# main.net
KiCad netlist of a schematic drawn in Altium Designer
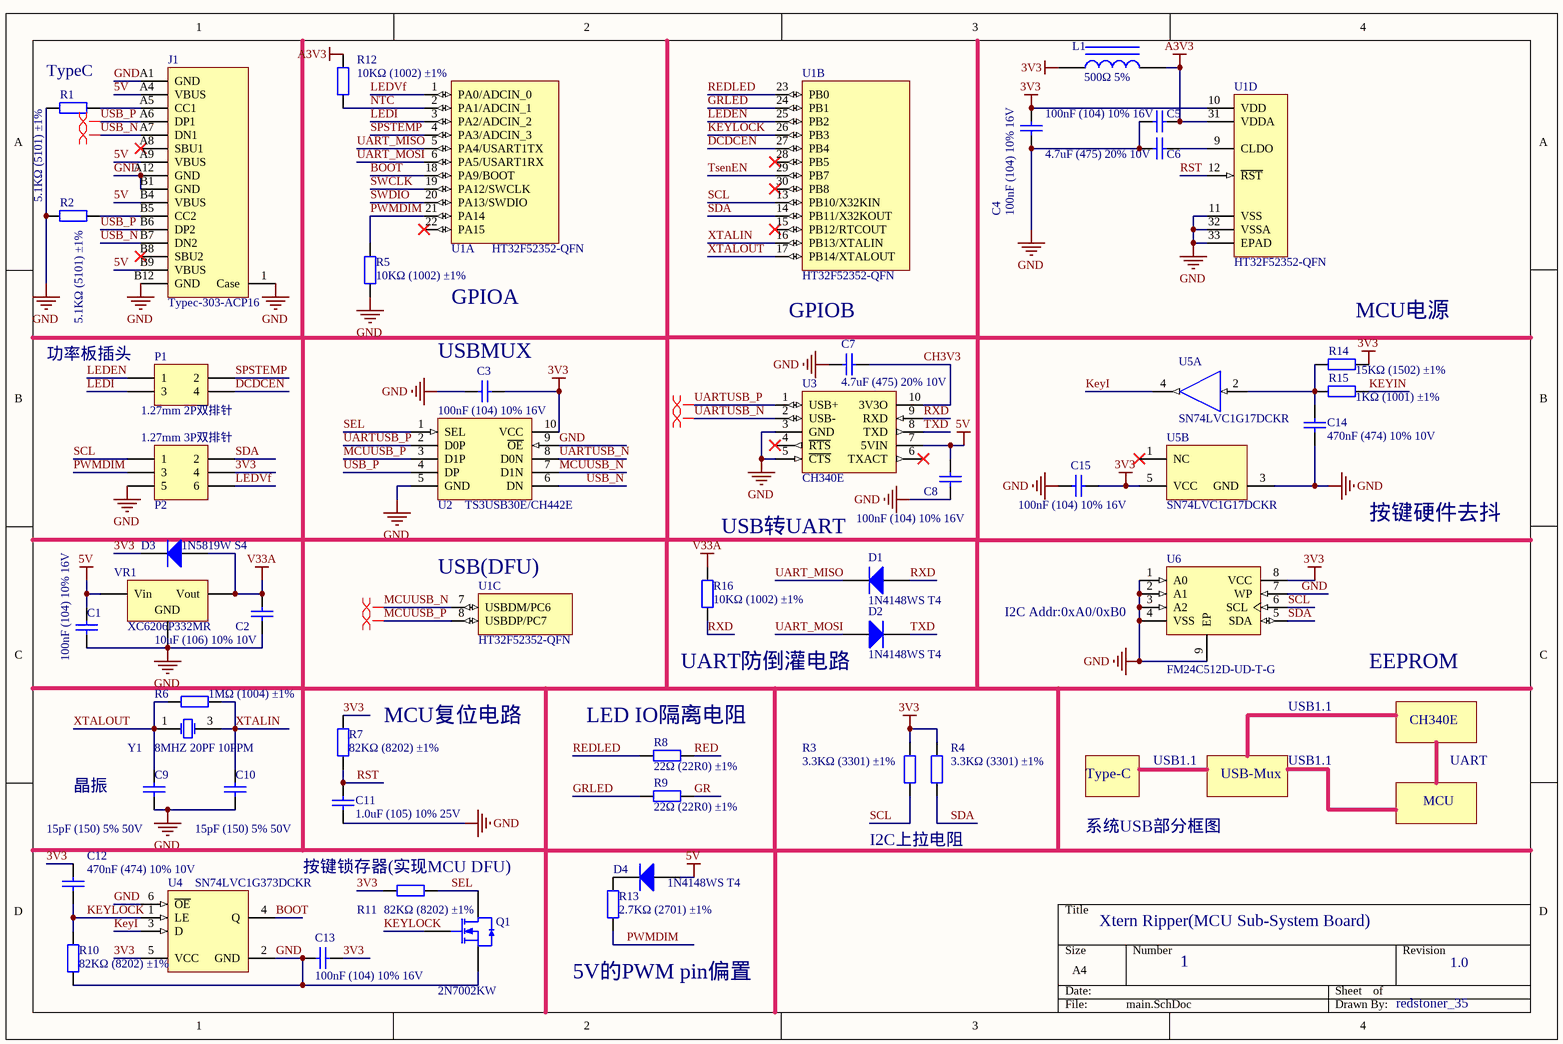
[diagram p0: main.SchDoc]

(export (version "E")
  (design (tool "Eeschema 10.0.6"))
  (components
    (comp (ref "C1")
      (value "100nF (104) 10% 16V")
      (footprint "0402_C")
      (description "贴片电容")
      (libsource (lib "Miscellaneous Devices LC") (part "0402 100nF (104) 10% 16V"))
    )
    (comp (ref "C2")
      (value "10uF (106) 10% 10V")
      (footprint "0603_C")
      (description "贴片电容")
      (libsource (lib "Miscellaneous Devices LC") (part "0603 10uF (106) 10% 10V"))
    )
    (comp (ref "C3")
      (value "100nF (104) 10% 16V")
      (footprint "0402_C")
      (description "贴片电容")
      (libsource (lib "Miscellaneous Devices LC") (part "0402 100nF (104) 10% 16V"))
    )
    (comp (ref "C4")
      (value "100nF (104) 10% 16V")
      (footprint "0402_C")
      (description "贴片电容")
      (libsource (lib "Miscellaneous Devices LC") (part "0402 100nF (104) 10% 16V"))
    )
    (comp (ref "C5")
      (value "100nF (104) 10% 16V")
      (footprint "0402_C")
      (description "贴片电容")
      (libsource (lib "Miscellaneous Devices LC") (part "0402 100nF (104) 10% 16V"))
    )
    (comp (ref "C6")
      (value "4.7uF (475) 20% 10V")
      (footprint "0402_C")
      (description "贴片电容")
      (libsource (lib "Miscellaneous Devices LC") (part "0402 4.7uF (475) 20% 10V"))
    )
    (comp (ref "C7")
      (value "4.7uF (475) 20% 10V")
      (footprint "0402_C")
      (description "贴片电容")
      (libsource (lib "Miscellaneous Devices LC") (part "0402 4.7uF (475) 20% 10V"))
    )
    (comp (ref "C8")
      (value "100nF (104) 10% 16V")
      (footprint "0402_C")
      (description "贴片电容")
      (libsource (lib "Miscellaneous Devices LC") (part "0402 100nF (104) 10% 16V"))
    )
    (comp (ref "C9")
      (value "15pF (150) 5% 50V")
      (footprint "0402_C")
      (description "贴片电容")
      (libsource (lib "Miscellaneous Devices LC") (part "0402 15pF (150) 5% 50V"))
    )
    (comp (ref "C10")
      (value "15pF (150) 5% 50V")
      (footprint "0402_C")
      (description "贴片电容")
      (libsource (lib "Miscellaneous Devices LC") (part "0402 15pF (150) 5% 50V"))
    )
    (comp (ref "C11")
      (value "1.0uF (105) 10% 25V")
      (footprint "0402_C")
      (description "贴片电容")
      (libsource (lib "Miscellaneous Devices LC") (part "0402 1.0uF (105) 10% 25V"))
    )
    (comp (ref "C12")
      (value "470nF (474) 10% 10V")
      (footprint "0402_C")
      (description "贴片电容")
      (libsource (lib "Miscellaneous Devices LC") (part "0402 470nF (474) 10% 10V"))
    )
    (comp (ref "C13")
      (value "100nF (104) 10% 16V")
      (footprint "0402_C")
      (description "贴片电容")
      (libsource (lib "Miscellaneous Devices LC") (part "0402 100nF (104) 10% 16V"))
    )
    (comp (ref "C14")
      (value "470nF (474) 10% 10V")
      (footprint "0402_C")
      (description "贴片电容")
      (libsource (lib "Miscellaneous Devices LC") (part "0402 470nF (474) 10% 10V"))
    )
    (comp (ref "C15")
      (value "100nF (104) 10% 16V")
      (footprint "0402_C")
      (description "贴片电容")
      (libsource (lib "Miscellaneous Devices LC") (part "0402 100nF (104) 10% 16V"))
    )
    (comp (ref "D1")
      (value "1N4148WS T4")
      (footprint "SOD-323")
      (description "二极管")
      (libsource (lib "Miscellaneous Devices LC") (part "SOD-323 1N4148WS T4"))
    )
    (comp (ref "D2")
      (value "1N4148WS T4")
      (footprint "SOD-323")
      (description "二极管")
      (libsource (lib "Miscellaneous Devices LC") (part "SOD-323 1N4148WS T4"))
    )
    (comp (ref "D3")
      (value "1N5819W S4")
      (footprint "SOD-323")
      (description "二极管")
      (libsource (lib "Miscellaneous Devices LC") (part "SOD-323 1N4148WS T4"))
    )
    (comp (ref "D4")
      (value "1N4148WS T4")
      (footprint "SOD-323")
      (description "二极管")
      (libsource (lib "Miscellaneous Devices LC") (part "SOD-323 1N4148WS T4"))
    )
    (comp (ref "J1")
      (value "Typec-303-ACP16")
      (footprint "USB-C-SMD_TYPEC-303-ACP16")
      (description "16Pin TypeC 立贴母座")
      (libsource (lib "custom") (part "Type-303-ACP16"))
    )
    (comp (ref "L1")
      (value "500Ω 5%")
      (footprint "0402_L")
      (description "贴片磁珠")
      (libsource (lib "Miscellaneous Devices LC") (part "0402 10nH 5%"))
    )
    (comp (ref "P1")
      (value "1.27mm 2P双排针")
      (footprint "MHDR2X2")
      (description "Header, 2-Pin, Dual row")
      (fields (field (name "PUBLISHER") "Altium Limited"))
      (libsource (lib "Miscellaneous Connectors") (part "MHDR2X2"))
    )
    (comp (ref "P2")
      (value "1.27mm 3P双排针")
      (footprint "MHDR2X3")
      (description "Header, 3-Pin, Dual row")
      (fields (field (name "PUBLISHER") "Altium Limited"))
      (libsource (lib "Miscellaneous Connectors") (part "MHDR2X3"))
    )
    (comp (ref "Q1")
      (value "2N7002KW")
      (footprint "SC70-3")
      (description "MOS(场效应管)")
      (libsource (lib "Miscellaneous Devices LC") (part "2N7002 7002"))
    )
    (comp (ref "R1")
      (value "5.1KΩ (5101) ±1%")
      (footprint "0402_R")
      (description "贴片电阻")
      (libsource (lib "Miscellaneous Devices LC") (part "0402 5.1KΩ (5101) 1%"))
    )
    (comp (ref "R2")
      (value "5.1KΩ (5101) ±1%")
      (footprint "0402_R")
      (description "贴片电阻")
      (libsource (lib "Miscellaneous Devices LC") (part "0402 5.1KΩ (5101) 1%"))
    )
    (comp (ref "R3")
      (value "3.3KΩ (3301) ±1%")
      (footprint "0402_R")
      (description "贴片电阻")
      (libsource (lib "Miscellaneous Devices LC") (part "0402 3.3KΩ (3301) 1%"))
    )
    (comp (ref "R4")
      (value "3.3KΩ (3301) ±1%")
      (footprint "0402_R")
      (description "贴片电阻")
      (libsource (lib "Miscellaneous Devices LC") (part "0402 3.3KΩ (3301) 1%"))
    )
    (comp (ref "R5")
      (value "10KΩ (1002) ±1%")
      (footprint "0402_R")
      (description "贴片电阻")
      (libsource (lib "Miscellaneous Devices LC") (part "0402 10KΩ (1002) 1%"))
    )
    (comp (ref "R6")
      (value "1MΩ (1004) ±1%")
      (footprint "0402_R")
      (description "贴片电阻")
      (libsource (lib "Miscellaneous Devices LC") (part "0402 1MΩ (1004) 1%"))
    )
    (comp (ref "R7")
      (value "82KΩ (8202) ±1%")
      (footprint "0402_R")
      (description "贴片电阻")
      (libsource (lib "Miscellaneous Devices LC") (part "0402 68KΩ (6802) 1%"))
    )
    (comp (ref "R8")
      (value "22Ω (22R0) ±1%")
      (footprint "0402_R")
      (description "贴片电阻")
      (libsource (lib "Miscellaneous Devices LC") (part "0402 22Ω (22R0) 1%"))
    )
    (comp (ref "R9")
      (value "22Ω (22R0) ±1%")
      (footprint "0402_R")
      (description "贴片电阻")
      (libsource (lib "Miscellaneous Devices LC") (part "0402 22Ω (22R0) 1%"))
    )
    (comp (ref "R10")
      (value "82KΩ (8202) ±1%")
      (footprint "0402_R")
      (description "贴片电阻")
      (libsource (lib "Miscellaneous Devices LC") (part "0402 68KΩ (6802) 1%"))
    )
    (comp (ref "R11")
      (value "82KΩ (8202) ±1%")
      (footprint "0402_R")
      (description "贴片电阻")
      (libsource (lib "Miscellaneous Devices LC") (part "0402 100KΩ (1003) 1%"))
    )
    (comp (ref "R12")
      (value "10KΩ (1002) ±1%")
      (footprint "0402_R")
      (description "贴片电阻")
      (libsource (lib "Miscellaneous Devices LC") (part "0402 10KΩ (1002) 1%"))
    )
    (comp (ref "R13")
      (value "2.7KΩ (2701) ±1%")
      (footprint "0402_R")
      (description "贴片电阻")
      (libsource (lib "Miscellaneous Devices LC") (part "0402 3.3KΩ (3301) 1%"))
    )
    (comp (ref "R14")
      (value "15KΩ (1502) ±1%")
      (footprint "0402_R")
      (description "贴片电阻")
      (libsource (lib "Miscellaneous Devices LC") (part "0402 15KΩ (1502) 1%"))
    )
    (comp (ref "R15")
      (value "1KΩ (1001) ±1%")
      (footprint "0402_R")
      (description "贴片电阻")
      (libsource (lib "Miscellaneous Devices LC") (part "0402 1KΩ (1001) 1%"))
    )
    (comp (ref "R16")
      (value "10KΩ (1002) ±1%")
      (footprint "0402_R")
      (description "贴片电阻")
      (libsource (lib "Miscellaneous Devices LC") (part "0402 10KΩ (1002) 1%"))
    )
    (comp (ref "U1")
      (value "HT32F52352-QFN")
      (footprint "QFN32-HT32")
      (description "Holtek MCU Cortex M0+ 48MHz 128K ROM 16K RAM")
      (libsource (lib "custom") (part "HT32F52352-QFN"))
    )
    (comp (ref "U2")
      (value "TS3USB30E/CH442E")
      (footprint "MSOP-10")
      (description "Passive SPDT USB2.0 Highspeed switch")
      (libsource (lib "custom") (part "TS3USB30E"))
    )
    (comp (ref "U3")
      (value "CH340E")
      (footprint "MSOP-10")
      (description "USB-TTL UART converter MSOP-10")
      (libsource (lib "custom") (part "CH340E"))
    )
    (comp (ref "U4")
      (value "SN74LVC1G373DCKR")
      (footprint "DCK0006A_N")
      (description "Single D-Type Latch with 3S Output, DCK0006A, LARGE T&R")
      (fields
        (field (name "GENERIC PART NUMBER") "SN74LVC1G373")
        (field (name "MANUFACTURER") "Texas Instruments")
      )
      (libsource (lib "TI_Logic_Little_Logic") (part "SN74LVC1G373DCKR"))
    )
    (comp (ref "U5")
      (value "SN74LVC1G17DCKR")
      (footprint "DCK0005A_N")
      (description "Single Schmitt-Trigger Buffer, DCK0005A, LARGE T&R")
      (fields
        (field (name "GENERIC PART NUMBER") "SN74LVC1G17")
        (field (name "MANUFACTURER") "Texas Instruments")
      )
      (libsource (lib "") (part "SN74LVC1G17DCKR_1"))
    )
    (comp (ref "U6")
      (value "FM24C512D-UD-T-G")
      (footprint "UDFN-8")
      (description "512Kbit 24Serires I2C EEPROM UDFN-8 with UID and OTP Sector")
      (libsource (lib "custom") (part "CAT24C512HU5"))
    )
    (comp (ref "VR1")
      (value "XC6206P332MR")
      (footprint "SOT-23-3L")
      (description "低压差线性稳压(LDO)")
      (libsource (lib "Miscellaneous Devices LC") (part "SOT-23 XC6206P332MR"))
    )
    (comp (ref "Y1")
      (value "8MHZ 20PF 10PPM")
      (footprint "SMD-3225_4P")
      (description "贴片晶振")
      (libsource (lib "Miscellaneous Devices LC") (part "SMD-3225_4P  12MHZ 20PF 10PPM"))
    )
  )
  (nets
    (net (code "1") (name "/BOOT") (class "Default")
      (node (ref "U1") (pin "18") (pinfunction "PA9/BOOT_18") (pintype "bidirectional"))
      (node (ref "U4") (pin "4") (pinfunction "Q_4") (pintype "tri_state"))
    )
    (net (code "2") (name "/CH3V3") (class "Default")
      (node (ref "C7") (pin "1") (pinfunction "1_1") (pintype "passive"))
      (node (ref "U3") (pin "10") (pinfunction "3V3O_10") (pintype "power_in"))
    )
    (net (code "3") (name "/DCDCEN") (class "Default")
      (node (ref "P1") (pin "4") (pinfunction "4_4") (pintype "passive"))
      (node (ref "U1") (pin "27") (pinfunction "PB4_27") (pintype "bidirectional"))
    )
    (net (code "4") (name "/GR") (class "Default")
      (node (ref "R9") (pin "2") (pinfunction "2_2") (pintype "passive"))
    )
    (net (code "5") (name "/GRLED") (class "Default")
      (node (ref "R9") (pin "1") (pinfunction "1_1") (pintype "passive"))
      (node (ref "U1") (pin "24") (pinfunction "PB1_24") (pintype "bidirectional"))
    )
    (net (code "6") (name "/KEYIN") (class "Default")
      (node (ref "R15") (pin "2") (pinfunction "2_2") (pintype "passive"))
    )
    (net (code "7") (name "/KEYLOCK") (class "Default")
      (node (ref "C12") (pin "1") (pinfunction "1_1") (pintype "passive"))
      (node (ref "Q1") (pin "1") (pinfunction "G_1") (pintype "passive"))
      (node (ref "R10") (pin "2") (pinfunction "2_2") (pintype "passive"))
      (node (ref "U1") (pin "26") (pinfunction "PB3_26") (pintype "bidirectional"))
      (node (ref "U4") (pin "1") (pinfunction "LE_1") (pintype "input"))
    )
    (net (code "8") (name "/KeyI") (class "Default")
      (node (ref "U4") (pin "3") (pinfunction "D_3") (pintype "input"))
      (node (ref "U5") (pin "4") (pinfunction "Y_4") (pintype "output"))
    )
    (net (code "9") (name "/LEDEN") (class "Default")
      (node (ref "P1") (pin "1") (pinfunction "1_1") (pintype "passive"))
      (node (ref "U1") (pin "25") (pinfunction "PB2_25") (pintype "bidirectional"))
    )
    (net (code "10") (name "/LEDI") (class "Default")
      (node (ref "P1") (pin "3") (pinfunction "3_3") (pintype "passive"))
      (node (ref "U1") (pin "3") (pinfunction "PA2/ADCIN_2_3") (pintype "bidirectional"))
    )
    (net (code "11") (name "/LEDVf") (class "Default")
      (node (ref "P2") (pin "6") (pinfunction "6_6") (pintype "passive"))
      (node (ref "U1") (pin "1") (pinfunction "PA0/ADCIN_0_1") (pintype "bidirectional"))
    )
    (net (code "12") (name "/MCUUSB_N") (class "Default")
      (node (ref "U1") (pin "7") (pinfunction "USBDM/PC6_7") (pintype "bidirectional"))
      (node (ref "U2") (pin "7") (pinfunction "D1N_7") (pintype "passive"))
    )
    (net (code "13") (name "/MCUUSB_P") (class "Default")
      (node (ref "U1") (pin "8") (pinfunction "USBDP/PC7_8") (pintype "bidirectional"))
      (node (ref "U2") (pin "3") (pinfunction "D1P_3") (pintype "passive"))
    )
    (net (code "14") (name "/NTC") (class "Default")
      (node (ref "R12") (pin "1") (pinfunction "1_1") (pintype "passive"))
      (node (ref "U1") (pin "2") (pinfunction "PA1/ADCIN_1_2") (pintype "bidirectional"))
    )
    (net (code "15") (name "/PWMDIM") (class "Default")
      (node (ref "P2") (pin "3") (pinfunction "3_3") (pintype "passive"))
      (node (ref "R13") (pin "1") (pinfunction "1_1") (pintype "passive"))
      (node (ref "R5") (pin "2") (pinfunction "2_2") (pintype "passive"))
      (node (ref "U1") (pin "21") (pinfunction "PA14_21") (pintype "bidirectional"))
    )
    (net (code "16") (name "/RED") (class "Default")
      (node (ref "R8") (pin "2") (pinfunction "2_2") (pintype "passive"))
    )
    (net (code "17") (name "/REDLED") (class "Default")
      (node (ref "R8") (pin "1") (pinfunction "1_1") (pintype "passive"))
      (node (ref "U1") (pin "23") (pinfunction "PB0_23") (pintype "bidirectional"))
    )
    (net (code "18") (name "/RST") (class "Default")
      (node (ref "C11") (pin "2") (pinfunction "2_2") (pintype "passive"))
      (node (ref "R7") (pin "1") (pinfunction "1_1") (pintype "passive"))
      (node (ref "U1") (pin "12") (pinfunction "~{RST}_12") (pintype "input"))
    )
    (net (code "19") (name "/RXD") (class "Default")
      (node (ref "D1") (pin "1") (pinfunction "A_1") (pintype "passive"))
      (node (ref "R16") (pin "1") (pinfunction "1_1") (pintype "passive"))
      (node (ref "U3") (pin "9") (pinfunction "RXD_9") (pintype "input"))
    )
    (net (code "20") (name "/SCL") (class "Default")
      (node (ref "P2") (pin "1") (pinfunction "1_1") (pintype "passive"))
      (node (ref "R3") (pin "1") (pinfunction "1_1") (pintype "passive"))
      (node (ref "U1") (pin "13") (pinfunction "PB10/X32KIN_13") (pintype "bidirectional"))
      (node (ref "U6") (pin "6") (pinfunction "SCL_6") (pintype "input"))
    )
    (net (code "21") (name "/SDA") (class "Default")
      (node (ref "P2") (pin "2") (pinfunction "2_2") (pintype "passive"))
      (node (ref "R4") (pin "1") (pinfunction "1_1") (pintype "passive"))
      (node (ref "U1") (pin "14") (pinfunction "PB11/X32KOUT_14") (pintype "bidirectional"))
      (node (ref "U6") (pin "5") (pinfunction "SDA_5") (pintype "bidirectional"))
    )
    (net (code "22") (name "/SEL") (class "Default")
      (node (ref "Q1") (pin "3") (pinfunction "D_3") (pintype "passive"))
      (node (ref "R11") (pin "2") (pinfunction "2_2") (pintype "passive"))
      (node (ref "U2") (pin "1") (pinfunction "SEL_1") (pintype "input"))
    )
    (net (code "23") (name "/SPSTEMP") (class "Default")
      (node (ref "P1") (pin "2") (pinfunction "2_2") (pintype "passive"))
      (node (ref "U1") (pin "4") (pinfunction "PA3/ADCIN_3_4") (pintype "bidirectional"))
    )
    (net (code "24") (name "/SWCLK") (class "Default")
      (node (ref "U1") (pin "19") (pinfunction "PA12/SWCLK_19") (pintype "bidirectional"))
    )
    (net (code "25") (name "/SWDIO") (class "Default")
      (node (ref "U1") (pin "20") (pinfunction "PA13/SWDIO_20") (pintype "bidirectional"))
    )
    (net (code "26") (name "/TXD") (class "Default")
      (node (ref "D2") (pin "2") (pinfunction "K_2") (pintype "passive"))
      (node (ref "U3") (pin "8") (pinfunction "TXD_8") (pintype "output"))
    )
    (net (code "27") (name "/TsenEN") (class "Default")
      (node (ref "U1") (pin "29") (pinfunction "PB7_29") (pintype "bidirectional"))
    )
    (net (code "28") (name "/UARTUSB_N") (class "Default")
      (node (ref "U2") (pin "8") (pinfunction "D0N_8") (pintype "passive"))
      (node (ref "U3") (pin "2") (pinfunction "USB-_2") (pintype "bidirectional"))
    )
    (net (code "29") (name "/UARTUSB_P") (class "Default")
      (node (ref "U2") (pin "2") (pinfunction "D0P_2") (pintype "passive"))
      (node (ref "U3") (pin "1") (pinfunction "USB+_1") (pintype "bidirectional"))
    )
    (net (code "30") (name "/UART_MISO") (class "Default")
      (node (ref "D1") (pin "2") (pinfunction "K_2") (pintype "passive"))
      (node (ref "U1") (pin "5") (pinfunction "PA4/USART1TX_5") (pintype "bidirectional"))
    )
    (net (code "31") (name "/UART_MOSI") (class "Default")
      (node (ref "D2") (pin "1") (pinfunction "A_1") (pintype "passive"))
      (node (ref "U1") (pin "6") (pinfunction "PA5/USART1RX_6") (pintype "bidirectional"))
    )
    (net (code "32") (name "/USB_N") (class "Default")
      (node (ref "J1") (pin "A7") (pinfunction "DN1_A7") (pintype "passive"))
      (node (ref "J1") (pin "B7") (pinfunction "DN2_B7") (pintype "passive"))
      (node (ref "U2") (pin "6") (pinfunction "DN_6") (pintype "power_in"))
    )
    (net (code "33") (name "/USB_P") (class "Default")
      (node (ref "J1") (pin "A6") (pinfunction "DP1_A6") (pintype "passive"))
      (node (ref "J1") (pin "B6") (pinfunction "DP2_B6") (pintype "passive"))
      (node (ref "U2") (pin "4") (pinfunction "DP_4") (pintype "passive"))
    )
    (net (code "34") (name "/XTALIN") (class "Default")
      (node (ref "C10") (pin "2") (pinfunction "2_2") (pintype "passive"))
      (node (ref "R6") (pin "2") (pinfunction "2_2") (pintype "passive"))
      (node (ref "U1") (pin "16") (pinfunction "PB13/XTALIN_16") (pintype "bidirectional"))
      (node (ref "Y1") (pin "3") (pinfunction "OSC2_3") (pintype "passive"))
    )
    (net (code "35") (name "/XTALOUT") (class "Default")
      (node (ref "C9") (pin "2") (pinfunction "2_2") (pintype "passive"))
      (node (ref "R6") (pin "1") (pinfunction "1_1") (pintype "passive"))
      (node (ref "U1") (pin "17") (pinfunction "PB14/XTALOUT_17") (pintype "bidirectional"))
      (node (ref "Y1") (pin "1") (pinfunction "OSC1_1") (pintype "passive"))
    )
    (net (code "36") (name "3V3") (class "Default")
      (node (ref "C12") (pin "2") (pinfunction "2_2") (pintype "passive"))
      (node (ref "C13") (pin "1") (pinfunction "1_1") (pintype "passive"))
      (node (ref "C15") (pin "2") (pinfunction "2_2") (pintype "passive"))
      (node (ref "C3") (pin "2") (pinfunction "2_2") (pintype "passive"))
      (node (ref "C4") (pin "2") (pinfunction "2_2") (pintype "passive"))
      (node (ref "D3") (pin "2") (pinfunction "K_2") (pintype "passive"))
      (node (ref "L1") (pin "1") (pinfunction "1_1") (pintype "passive"))
      (node (ref "P2") (pin "4") (pinfunction "4_4") (pintype "passive"))
      (node (ref "R11") (pin "1") (pinfunction "1_1") (pintype "passive"))
      (node (ref "R14") (pin "1") (pinfunction "1_1") (pintype "passive"))
      (node (ref "R3") (pin "2") (pinfunction "2_2") (pintype "passive"))
      (node (ref "R4") (pin "2") (pinfunction "2_2") (pintype "passive"))
      (node (ref "R7") (pin "2") (pinfunction "2_2") (pintype "passive"))
      (node (ref "U1") (pin "10") (pinfunction "VDD_10") (pintype "power_in"))
      (node (ref "U2") (pin "10") (pinfunction "VCC_10") (pintype "power_in"))
      (node (ref "U4") (pin "5") (pinfunction "VCC_5") (pintype "power_in"))
      (node (ref "U5") (pin "5") (pinfunction "VCC_5") (pintype "power_in"))
      (node (ref "U6") (pin "8") (pinfunction "VCC_8") (pintype "power_in"))
    )
    (net (code "37") (name "5V") (class "Default")
      (node (ref "C1") (pin "2") (pinfunction "2_2") (pintype "passive"))
      (node (ref "C8") (pin "2") (pinfunction "2_2") (pintype "passive"))
      (node (ref "D4") (pin "1") (pinfunction "A_1") (pintype "passive"))
      (node (ref "J1") (pin "A4") (pinfunction "VBUS_A4") (pintype "passive"))
      (node (ref "J1") (pin "A9") (pinfunction "VBUS_A9") (pintype "passive"))
      (node (ref "J1") (pin "B4") (pinfunction "VBUS_B4") (pintype "passive"))
      (node (ref "J1") (pin "B9") (pinfunction "VBUS_B9") (pintype "passive"))
      (node (ref "U3") (pin "7") (pinfunction "5VIN_7") (pintype "power_in"))
      (node (ref "VR1") (pin "3") (pinfunction "Vin_3") (pintype "passive"))
    )
    (net (code "38") (name "A3V3") (class "Default")
      (node (ref "C5") (pin "1") (pinfunction "1_1") (pintype "passive"))
      (node (ref "L1") (pin "2") (pinfunction "2_2") (pintype "passive"))
      (node (ref "R12") (pin "2") (pinfunction "2_2") (pintype "passive"))
      (node (ref "U1") (pin "31") (pinfunction "VDDA_31") (pintype "power_in"))
    )
    (net (code "39") (name "GND") (class "Default")
      (node (ref "C1") (pin "1") (pinfunction "1_1") (pintype "passive"))
      (node (ref "C10") (pin "1") (pinfunction "1_1") (pintype "passive"))
      (node (ref "C11") (pin "1") (pinfunction "1_1") (pintype "passive"))
      (node (ref "C13") (pin "2") (pinfunction "2_2") (pintype "passive"))
      (node (ref "C14") (pin "1") (pinfunction "1_1") (pintype "passive"))
      (node (ref "C15") (pin "1") (pinfunction "1_1") (pintype "passive"))
      (node (ref "C2") (pin "1") (pinfunction "1_1") (pintype "passive"))
      (node (ref "C3") (pin "1") (pinfunction "1_1") (pintype "passive"))
      (node (ref "C4") (pin "1") (pinfunction "1_1") (pintype "passive"))
      (node (ref "C5") (pin "2") (pinfunction "2_2") (pintype "passive"))
      (node (ref "C6") (pin "2") (pinfunction "2_2") (pintype "passive"))
      (node (ref "C7") (pin "2") (pinfunction "2_2") (pintype "passive"))
      (node (ref "C8") (pin "1") (pinfunction "1_1") (pintype "passive"))
      (node (ref "C9") (pin "1") (pinfunction "1_1") (pintype "passive"))
      (node (ref "J1") (pin "1") (pinfunction "Case_1") (pintype "passive"))
      (node (ref "J1") (pin "A1") (pinfunction "GND_A1") (pintype "passive"))
      (node (ref "J1") (pin "A12") (pinfunction "GND_A12") (pintype "passive"))
      (node (ref "J1") (pin "B1") (pinfunction "GND_B1") (pintype "passive"))
      (node (ref "J1") (pin "B12") (pinfunction "GND_B12") (pintype "passive"))
      (node (ref "P2") (pin "5") (pinfunction "5_5") (pintype "passive"))
      (node (ref "Q1") (pin "2") (pinfunction "S_2") (pintype "passive"))
      (node (ref "R1") (pin "1") (pinfunction "1_1") (pintype "passive"))
      (node (ref "R10") (pin "1") (pinfunction "1_1") (pintype "passive"))
      (node (ref "R2") (pin "1") (pinfunction "1_1") (pintype "passive"))
      (node (ref "R5") (pin "1") (pinfunction "1_1") (pintype "passive"))
      (node (ref "U1") (pin "11") (pinfunction "VSS_11") (pintype "power_in"))
      (node (ref "U1") (pin "32") (pinfunction "VSSA_32") (pintype "power_in"))
      (node (ref "U1") (pin "33") (pinfunction "EPAD_33") (pintype "power_in"))
      (node (ref "U2") (pin "5") (pinfunction "GND_5") (pintype "power_in"))
      (node (ref "U2") (pin "9") (pinfunction "~{OE}_9") (pintype "input"))
      (node (ref "U3") (pin "3") (pinfunction "GND_3") (pintype "power_in"))
      (node (ref "U3") (pin "5") (pinfunction "~{CTS}_5") (pintype "input"))
      (node (ref "U4") (pin "2") (pinfunction "GND_2") (pintype "power_in"))
      (node (ref "U4") (pin "6") (pinfunction "~{OE}_6") (pintype "input"))
      (node (ref "U5") (pin "3") (pinfunction "GND_3") (pintype "power_in"))
      (node (ref "U6") (pin "1") (pinfunction "A0_1") (pintype "input"))
      (node (ref "U6") (pin "2") (pinfunction "A1_2") (pintype "input"))
      (node (ref "U6") (pin "3") (pinfunction "A2_3") (pintype "input"))
      (node (ref "U6") (pin "4") (pinfunction "VSS_4") (pintype "power_in"))
      (node (ref "U6") (pin "7") (pinfunction "WP_7") (pintype "input"))
      (node (ref "U6") (pin "9") (pinfunction "EP_9") (pintype "power_in"))
      (node (ref "VR1") (pin "1") (pinfunction "GND_1") (pintype "passive"))
    )
    (net (code "40") (name "Net-(D4-K)") (class "Default")
      (node (ref "D4") (pin "2") (pinfunction "K_2") (pintype "passive"))
      (node (ref "R13") (pin "2") (pinfunction "2_2") (pintype "passive"))
    )
    (net (code "41") (name "Net-(J1-CC1)") (class "Default")
      (node (ref "J1") (pin "A5") (pinfunction "CC1_A5") (pintype "passive"))
      (node (ref "R1") (pin "2") (pinfunction "2_2") (pintype "passive"))
    )
    (net (code "42") (name "Net-(J1-CC2)") (class "Default")
      (node (ref "J1") (pin "B5") (pinfunction "CC2_B5") (pintype "passive"))
      (node (ref "R2") (pin "2") (pinfunction "2_2") (pintype "passive"))
    )
    (net (code "43") (name "Net-(U1D-CLDO)") (class "Default")
      (node (ref "C6") (pin "1") (pinfunction "1_1") (pintype "passive"))
      (node (ref "U1") (pin "9") (pinfunction "CLDO_9") (pintype "power_in"))
    )
    (net (code "44") (name "Net-(U5A-A)") (class "Default")
      (node (ref "C14") (pin "2") (pinfunction "2_2") (pintype "passive"))
      (node (ref "R14") (pin "2") (pinfunction "2_2") (pintype "passive"))
      (node (ref "R15") (pin "1") (pinfunction "1_1") (pintype "passive"))
      (node (ref "U5") (pin "2") (pinfunction "A_2") (pintype "input"))
    )
    (net (code "45") (name "V33A") (class "Default")
      (node (ref "C2") (pin "2") (pinfunction "2_2") (pintype "passive"))
      (node (ref "D3") (pin "1") (pinfunction "A_1") (pintype "passive"))
      (node (ref "R16") (pin "2") (pinfunction "2_2") (pintype "passive"))
      (node (ref "VR1") (pin "2") (pinfunction "Vout_2") (pintype "passive"))
    )
    (net (code "46") (name "unconnected-(J1-SBU1-PadA8)") (class "Default")
      (node (ref "J1") (pin "A8") (pinfunction "SBU1_A8") (pintype "passive+no_connect"))
    )
    (net (code "47") (name "unconnected-(J1-SBU2-PadB8)") (class "Default")
      (node (ref "J1") (pin "B8") (pinfunction "SBU2_B8") (pintype "passive+no_connect"))
    )
    (net (code "48") (name "unconnected-(U1A-PA15-Pad22)") (class "Default")
      (node (ref "U1") (pin "22") (pinfunction "PA15_22") (pintype "bidirectional+no_connect"))
    )
    (net (code "49") (name "unconnected-(U1B-PB5-Pad28)") (class "Default")
      (node (ref "U1") (pin "28") (pinfunction "PB5_28") (pintype "bidirectional+no_connect"))
    )
    (net (code "50") (name "unconnected-(U1B-PB8-Pad30)") (class "Default")
      (node (ref "U1") (pin "30") (pinfunction "PB8_30") (pintype "bidirectional+no_connect"))
    )
    (net (code "51") (name "unconnected-(U1B-PB12{slash}RTCOUT-Pad15)") (class "Default")
      (node (ref "U1") (pin "15") (pinfunction "PB12/RTCOUT_15") (pintype "bidirectional+no_connect"))
    )
    (net (code "52") (name "unconnected-(U3-TXACT-Pad6)") (class "Default")
      (node (ref "U3") (pin "6") (pinfunction "TXACT_6") (pintype "output+no_connect"))
    )
    (net (code "53") (name "unconnected-(U3-~{RTS}-Pad4)") (class "Default")
      (node (ref "U3") (pin "4") (pinfunction "~{RTS}_4") (pintype "output+no_connect"))
    )
    (net (code "54") (name "unconnected-(U5B-NC-Pad1)") (class "Default")
      (node (ref "U5") (pin "1") (pinfunction "NC_1") (pintype "passive+no_connect"))
    )
  )
)
